# node_rgb.net
KiCad netlist of a schematic drawn in EAGLE
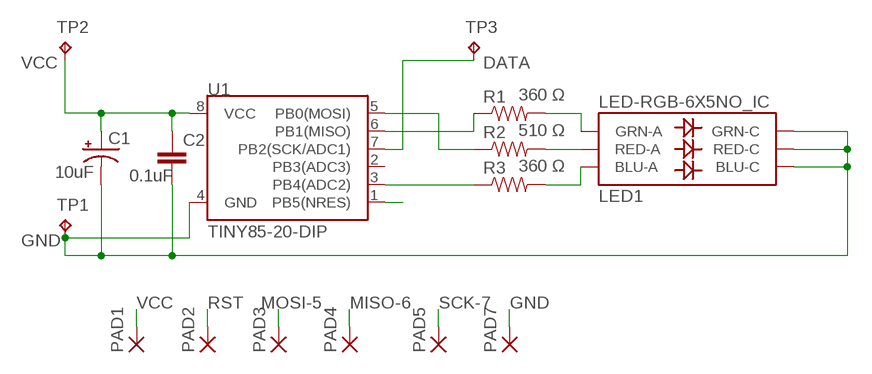
[diagram p0: schematic, sheet 1]

(export (version "E")
  (design (tool "Eeschema 10.0.6"))
  (components
    (comp (ref "C1")
      (value "10uF")
      (footprint "eagle-import:EIA3216")
      (libsource (lib "eagle-import") (part "10UF-16V-10%(TANT)"))
    )
    (comp (ref "C2")
      (value "0.1uF")
      (footprint "eagle-import:1206")
      (libsource (lib "eagle-import") (part "CAP1206"))
    )
    (comp (ref "LED1")
      (value "LED-RGB-6X5NO_IC")
      (footprint "eagle-import:LED-RGB-6X5")
      (libsource (lib "eagle-import") (part "LED-RGB-6X5NO_IC"))
    )
    (comp (ref "PAD1")
      (value "SMD5")
      (footprint "eagle-import:SMD2,54-5,08")
      (libsource (lib "eagle-import") (part "SMD5"))
    )
    (comp (ref "PAD2")
      (value "SMD5")
      (footprint "eagle-import:SMD2,54-5,08")
      (libsource (lib "eagle-import") (part "SMD5"))
    )
    (comp (ref "PAD3")
      (value "SMD5")
      (footprint "eagle-import:SMD2,54-5,08")
      (libsource (lib "eagle-import") (part "SMD5"))
    )
    (comp (ref "PAD4")
      (value "SMD5")
      (footprint "eagle-import:SMD2,54-5,08")
      (libsource (lib "eagle-import") (part "SMD5"))
    )
    (comp (ref "PAD5")
      (value "SMD5")
      (footprint "eagle-import:SMD2,54-5,08")
      (libsource (lib "eagle-import") (part "SMD5"))
    )
    (comp (ref "PAD7")
      (value "SMD5")
      (footprint "eagle-import:SMD2,54-5,08")
      (libsource (lib "eagle-import") (part "SMD5"))
    )
    (comp (ref "R1")
      (value "360 Ω")
      (footprint "eagle-import:1206")
      (libsource (lib "eagle-import") (part "RESISTOR1206"))
    )
    (comp (ref "R2")
      (value "510 Ω")
      (footprint "eagle-import:1206")
      (libsource (lib "eagle-import") (part "RESISTOR1206"))
    )
    (comp (ref "R3")
      (value "360 Ω ")
      (footprint "eagle-import:1206")
      (libsource (lib "eagle-import") (part "RESISTOR1206"))
    )
    (comp (ref "TP1")
      (value "PADSTP13R")
      (footprint "eagle-import:CIRCLE-PAD-1_4")
      (fields (field (name "TP_SIGNAL_NAME") "GND"))
      (libsource (lib "eagle-import") (part "PADSTP13R"))
    )
    (comp (ref "TP2")
      (value "PADSTP13R")
      (footprint "eagle-import:CIRCLE-PAD-1_4")
      (fields (field (name "TP_SIGNAL_NAME") "VCC"))
      (libsource (lib "eagle-import") (part "PADSTP13R"))
    )
    (comp (ref "TP3")
      (value "PADSTP13R")
      (footprint "eagle-import:CIRCLE-PAD-1_4")
      (fields (field (name "TP_SIGNAL_NAME") "DATA"))
      (libsource (lib "eagle-import") (part "PADSTP13R"))
    )
    (comp (ref "U1")
      (value "TINY85-20-DIP")
      (footprint "eagle-import:DIP08")
      (libsource (lib "eagle-import") (part "ATTINY45TINY45-20-DIP"))
    )
  )
  (nets
    (net (code "1") (name "/GND") (class "Default")
      (node (ref "C1") (pin "C") (pinfunction "-_C") (pintype "passive"))
      (node (ref "C2") (pin "2") (pinfunction "2_2") (pintype "passive"))
      (node (ref "LED1") (pin "1") (pinfunction "BLU-C_1") (pintype "bidirectional"))
      (node (ref "LED1") (pin "2") (pinfunction "RED-C_2") (pintype "bidirectional"))
      (node (ref "LED1") (pin "3") (pinfunction "GRN-C_3") (pintype "bidirectional"))
      (node (ref "PAD7") (pin "1") (pinfunction "P_1") (pintype "passive"))
      (node (ref "TP1") (pin "TP") (pinfunction "TP_TP") (pintype "input"))
      (node (ref "U1") (pin "4") (pinfunction "GND_4") (pintype "bidirectional"))
    )
    (net (code "2") (name "/MISO-6") (class "Default")
      (node (ref "PAD4") (pin "1") (pinfunction "P_1") (pintype "passive"))
      (node (ref "R1") (pin "1") (pinfunction "1_1") (pintype "passive"))
      (node (ref "U1") (pin "6") (pinfunction "PB1(MISO)_6") (pintype "bidirectional"))
    )
    (net (code "3") (name "/MOSI-5") (class "Default")
      (node (ref "PAD3") (pin "1") (pinfunction "P_1") (pintype "passive"))
      (node (ref "R2") (pin "1") (pinfunction "1_1") (pintype "passive"))
      (node (ref "U1") (pin "5") (pinfunction "PB0(MOSI)_5") (pintype "bidirectional"))
    )
    (net (code "4") (name "/RST") (class "Default")
      (node (ref "PAD2") (pin "1") (pinfunction "P_1") (pintype "passive"))
      (node (ref "U1") (pin "1") (pinfunction "PB5(NRES)_1") (pintype "bidirectional"))
    )
    (net (code "5") (name "/SCK-7") (class "Default")
      (node (ref "PAD5") (pin "1") (pinfunction "P_1") (pintype "passive"))
      (node (ref "TP3") (pin "TP") (pinfunction "TP_TP") (pintype "input"))
      (node (ref "U1") (pin "7") (pinfunction "PB2(SCK/ADC1)_7") (pintype "bidirectional"))
    )
    (net (code "6") (name "/VCC") (class "Default")
      (node (ref "C1") (pin "A") (pinfunction "+_A") (pintype "passive"))
      (node (ref "C2") (pin "1") (pinfunction "1_1") (pintype "passive"))
      (node (ref "PAD1") (pin "1") (pinfunction "P_1") (pintype "passive"))
      (node (ref "TP2") (pin "TP") (pinfunction "TP_TP") (pintype "input"))
      (node (ref "U1") (pin "8") (pinfunction "VCC_8") (pintype "bidirectional"))
    )
    (net (code "7") (name "Net-(LED1-BLU-A)") (class "Default")
      (node (ref "LED1") (pin "6") (pinfunction "BLU-A_6") (pintype "bidirectional"))
      (node (ref "R3") (pin "2") (pinfunction "2_2") (pintype "passive"))
    )
    (net (code "8") (name "Net-(LED1-GRN-A)") (class "Default")
      (node (ref "LED1") (pin "4") (pinfunction "GRN-A_4") (pintype "bidirectional"))
      (node (ref "R1") (pin "2") (pinfunction "2_2") (pintype "passive"))
    )
    (net (code "9") (name "Net-(LED1-RED-A)") (class "Default")
      (node (ref "LED1") (pin "5") (pinfunction "RED-A_5") (pintype "bidirectional"))
      (node (ref "R2") (pin "2") (pinfunction "2_2") (pintype "passive"))
    )
    (net (code "10") (name "Net-(U1-PB4(ADC2))") (class "Default")
      (node (ref "R3") (pin "1") (pinfunction "1_1") (pintype "passive"))
      (node (ref "U1") (pin "3") (pinfunction "PB4(ADC2)_3") (pintype "bidirectional"))
    )
    (net (code "11") (name "unconnected-(U1-PB3(ADC3)-Pad2)") (class "Default")
      (node (ref "U1") (pin "2") (pinfunction "PB3(ADC3)_2") (pintype "bidirectional"))
    )
  )
)
